# Sampling_Detector.net
KiCad netlist of a schematic drawn in EAGLE
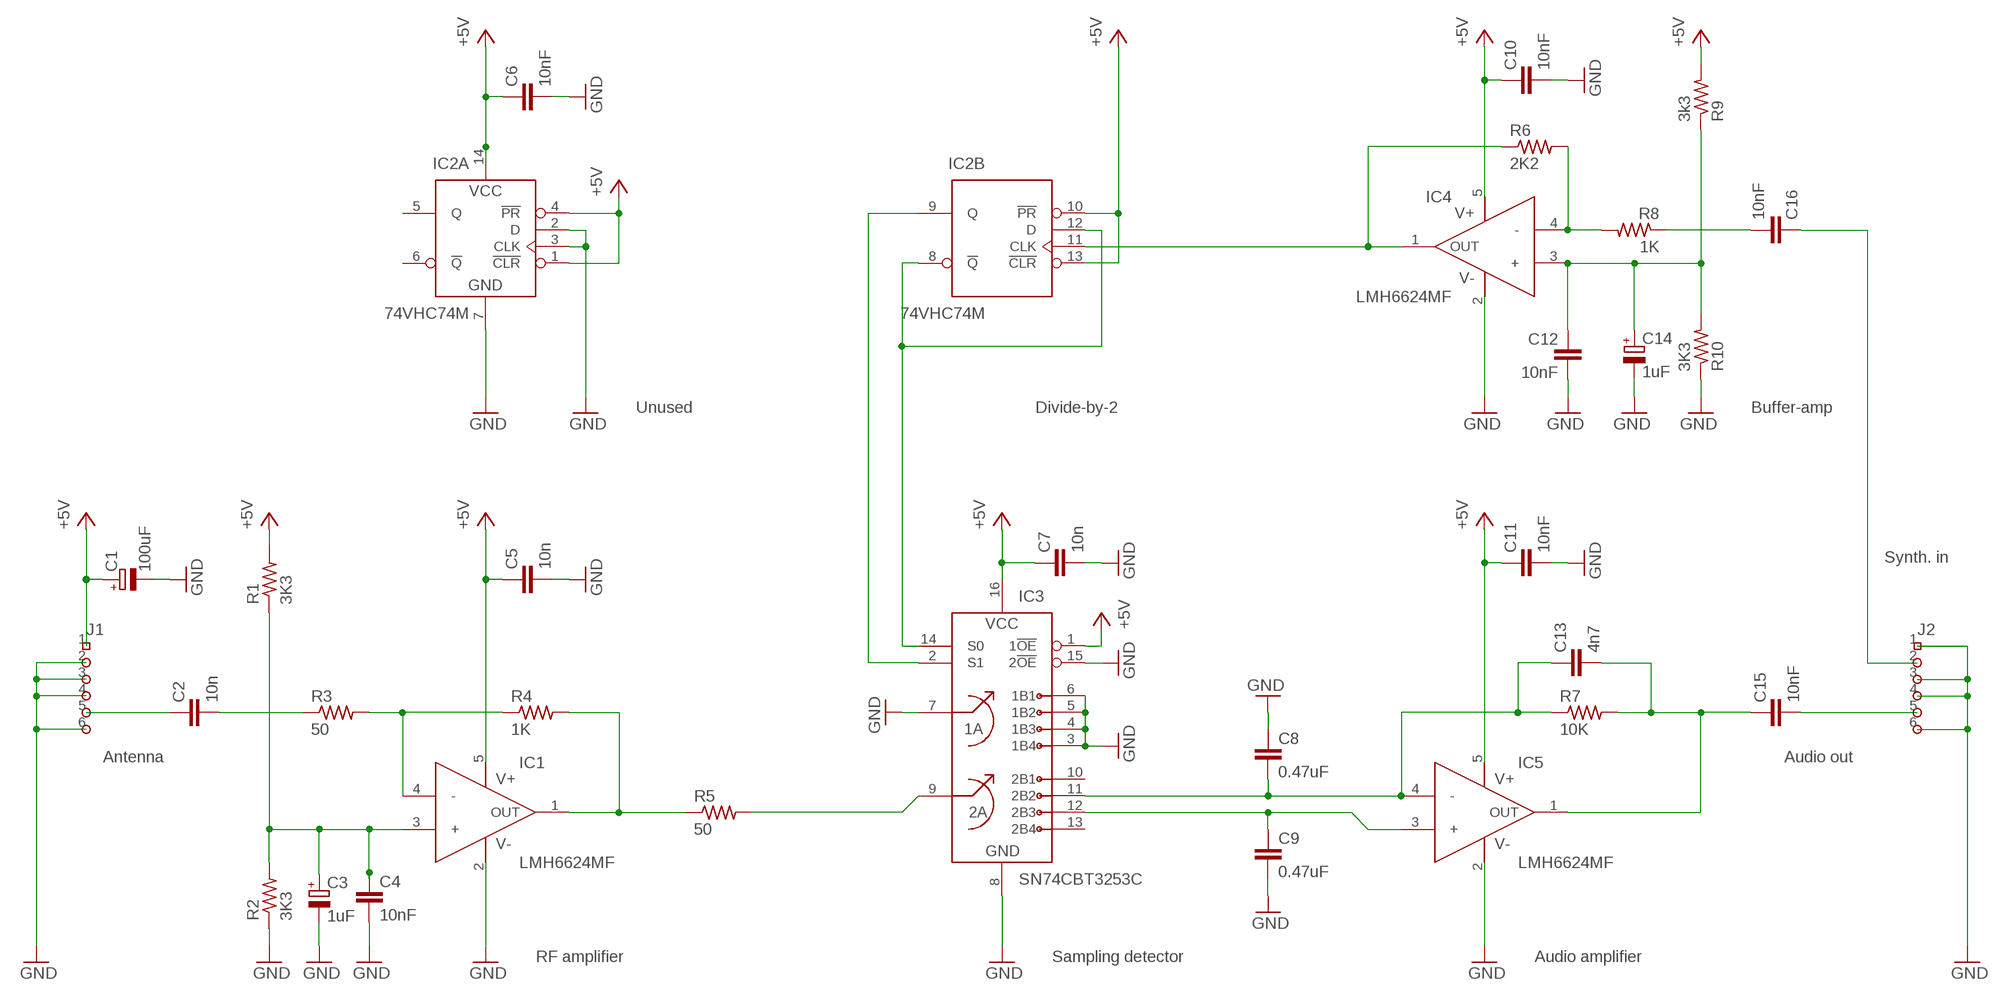
[diagram p0: schematic, sheet 1]

(export (version "E")
  (design (tool "Eeschema 10.0.6"))
  (components
    (comp (ref "C1")
      (value "100uF")
      (footprint "eagle-import:E5.8-8")
      (libsource (lib "eagle-import") (part "ELECTROLYTIC-PIGTAIL"))
    )
    (comp (ref "C2")
      (value "10n")
      (footprint "eagle-import:SMD-0805")
      (libsource (lib "eagle-import") (part "CAPACITOR-0805"))
    )
    (comp (ref "C3")
      (value "1uF")
      (footprint "eagle-import:SMD-0805")
      (libsource (lib "eagle-import") (part "ELECTROLYTIC-0805"))
    )
    (comp (ref "C4")
      (value "10nF")
      (footprint "eagle-import:SMD-0805")
      (libsource (lib "eagle-import") (part "CAPACITOR-0805"))
    )
    (comp (ref "C5")
      (value "10n")
      (footprint "eagle-import:SMD-0805")
      (libsource (lib "eagle-import") (part "CAPACITOR-0805"))
    )
    (comp (ref "C6")
      (value "10nF")
      (footprint "eagle-import:SMD-0805")
      (libsource (lib "eagle-import") (part "CAPACITOR-0805"))
    )
    (comp (ref "C7")
      (value "10n")
      (footprint "eagle-import:SMD-0805")
      (libsource (lib "eagle-import") (part "CAPACITOR-0805"))
    )
    (comp (ref "C8")
      (value "0.47uF")
      (footprint "eagle-import:SMD-0805")
      (libsource (lib "eagle-import") (part "CAPACITOR-0805"))
    )
    (comp (ref "C9")
      (value "0.47uF")
      (footprint "eagle-import:SMD-0805")
      (libsource (lib "eagle-import") (part "CAPACITOR-0805"))
    )
    (comp (ref "C10")
      (value "10nF")
      (footprint "eagle-import:SMD-0805")
      (libsource (lib "eagle-import") (part "CAPACITOR-0805"))
    )
    (comp (ref "C11")
      (value "10nF")
      (footprint "eagle-import:SMD-0805")
      (libsource (lib "eagle-import") (part "CAPACITOR-0805"))
    )
    (comp (ref "C12")
      (value "10nF")
      (footprint "eagle-import:SMD-0805")
      (libsource (lib "eagle-import") (part "CAPACITOR-0805"))
    )
    (comp (ref "C13")
      (value "4n7")
      (footprint "eagle-import:SMD-0805")
      (libsource (lib "eagle-import") (part "CAPACITOR-0805"))
    )
    (comp (ref "C14")
      (value "1uF")
      (footprint "eagle-import:SMD-0805")
      (libsource (lib "eagle-import") (part "ELECTROLYTIC-0805"))
    )
    (comp (ref "C15")
      (value "10nF")
      (footprint "eagle-import:SMD-0805")
      (libsource (lib "eagle-import") (part "CAPACITOR-0805"))
    )
    (comp (ref "C16")
      (value "10nF")
      (footprint "eagle-import:SMD-0805")
      (libsource (lib "eagle-import") (part "CAPACITOR-0805"))
    )
    (comp (ref "IC1")
      (value "LMH6624MF")
      (footprint "eagle-import:SOT-23-DBV")
      (libsource (lib "eagle-import") (part "LMH6624MF"))
    )
    (comp (ref "IC2")
      (value "74VHC74M")
      (footprint "eagle-import:SOIC-14PIN")
      (libsource (lib "eagle-import") (part "74VHC74M"))
    )
    (comp (ref "IC3")
      (value "SN74CBT3253C")
      (footprint "eagle-import:SOIC-16PIN")
      (libsource (lib "eagle-import") (part "SN74CBT3253C"))
    )
    (comp (ref "IC4")
      (value "LMH6624MF")
      (footprint "eagle-import:SOT-23-DBV")
      (libsource (lib "eagle-import") (part "LMH6624MF"))
    )
    (comp (ref "IC5")
      (value "LMH6624MF")
      (footprint "eagle-import:SOT-23-DBV")
      (libsource (lib "eagle-import") (part "LMH6624MF"))
    )
    (comp (ref "J1")
      (value "TERM-STRIP-6PIN")
      (footprint "eagle-import:TERM-STRIP-6PIN")
      (libsource (lib "eagle-import") (part "TERM-STRIP-6PIN"))
    )
    (comp (ref "J2")
      (value "TERM-STRIP-6PIN")
      (footprint "eagle-import:TERM-STRIP-6PIN")
      (libsource (lib "eagle-import") (part "TERM-STRIP-6PIN"))
    )
    (comp (ref "R1")
      (value "3K3")
      (footprint "eagle-import:SMD-0805")
      (libsource (lib "eagle-import") (part "RESISTOR-0805"))
    )
    (comp (ref "R2")
      (value "3K3")
      (footprint "eagle-import:SMD-0805")
      (libsource (lib "eagle-import") (part "RESISTOR-0805"))
    )
    (comp (ref "R3")
      (value "50")
      (footprint "eagle-import:SMD-0805")
      (libsource (lib "eagle-import") (part "RESISTOR-0805"))
    )
    (comp (ref "R4")
      (value "1K")
      (footprint "eagle-import:SMD-0805")
      (libsource (lib "eagle-import") (part "RESISTOR-0805"))
    )
    (comp (ref "R5")
      (value "50")
      (footprint "eagle-import:SMD-0805")
      (libsource (lib "eagle-import") (part "RESISTOR-0805"))
    )
    (comp (ref "R6")
      (value "2K2")
      (footprint "eagle-import:SMD-0805")
      (libsource (lib "eagle-import") (part "RESISTOR-0805"))
    )
    (comp (ref "R7")
      (value "10K")
      (footprint "eagle-import:SMD-0805")
      (libsource (lib "eagle-import") (part "RESISTOR-0805"))
    )
    (comp (ref "R8")
      (value "1K")
      (footprint "eagle-import:SMD-0805")
      (libsource (lib "eagle-import") (part "RESISTOR-0805"))
    )
    (comp (ref "R9")
      (value "3k3")
      (footprint "eagle-import:SMD-0805")
      (libsource (lib "eagle-import") (part "RESISTOR-0805"))
    )
    (comp (ref "R10")
      (value "3K3")
      (footprint "eagle-import:SMD-0805")
      (libsource (lib "eagle-import") (part "RESISTOR-0805"))
    )
  )
  (nets
    (net (code "1") (name "+5V") (class "Default")
      (node (ref "C1") (pin "1") (pinfunction "+_1") (pintype "passive"))
      (node (ref "C10") (pin "1") (pinfunction "1_1") (pintype "passive"))
      (node (ref "C11") (pin "1") (pinfunction "1_1") (pintype "passive"))
      (node (ref "C5") (pin "1") (pinfunction "1_1") (pintype "passive"))
      (node (ref "C6") (pin "1") (pinfunction "1_1") (pintype "passive"))
      (node (ref "C7") (pin "1") (pinfunction "1_1") (pintype "passive"))
      (node (ref "IC1") (pin "5") (pinfunction "V+_5") (pintype "power_in"))
      (node (ref "IC2") (pin "1") (pinfunction "~{CLR}_1") (pintype "input"))
      (node (ref "IC2") (pin "10") (pinfunction "~{PR}_10") (pintype "input"))
      (node (ref "IC2") (pin "13") (pinfunction "~{CLR}_13") (pintype "input"))
      (node (ref "IC2") (pin "14") (pinfunction "VCC_14") (pintype "power_in"))
      (node (ref "IC2") (pin "4") (pinfunction "~{PR}_4") (pintype "input"))
      (node (ref "IC3") (pin "1") (pinfunction "1~{OE}_1") (pintype "input"))
      (node (ref "IC3") (pin "16") (pinfunction "VCC_16") (pintype "power_in"))
      (node (ref "IC4") (pin "5") (pinfunction "V+_5") (pintype "power_in"))
      (node (ref "IC5") (pin "5") (pinfunction "V+_5") (pintype "power_in"))
      (node (ref "J1") (pin "1") (pinfunction "1_1") (pintype "bidirectional"))
      (node (ref "R1") (pin "2") (pinfunction "2_2") (pintype "passive"))
      (node (ref "R9") (pin "2") (pinfunction "2_2") (pintype "passive"))
    )
    (net (code "2") (name "GND") (class "Default")
      (node (ref "C1") (pin "2") (pinfunction "-_2") (pintype "passive"))
      (node (ref "C10") (pin "2") (pinfunction "2_2") (pintype "passive"))
      (node (ref "C11") (pin "2") (pinfunction "2_2") (pintype "passive"))
      (node (ref "C12") (pin "2") (pinfunction "2_2") (pintype "passive"))
      (node (ref "C14") (pin "2") (pinfunction "-_2") (pintype "passive"))
      (node (ref "C3") (pin "2") (pinfunction "-_2") (pintype "passive"))
      (node (ref "C4") (pin "2") (pinfunction "2_2") (pintype "passive"))
      (node (ref "C5") (pin "2") (pinfunction "2_2") (pintype "passive"))
      (node (ref "C6") (pin "2") (pinfunction "2_2") (pintype "passive"))
      (node (ref "C7") (pin "2") (pinfunction "2_2") (pintype "passive"))
      (node (ref "C8") (pin "1") (pinfunction "1_1") (pintype "passive"))
      (node (ref "C9") (pin "2") (pinfunction "2_2") (pintype "passive"))
      (node (ref "IC1") (pin "2") (pinfunction "V-_2") (pintype "power_in"))
      (node (ref "IC2") (pin "2") (pinfunction "D_2") (pintype "input"))
      (node (ref "IC2") (pin "3") (pinfunction "CLK_3") (pintype "input"))
      (node (ref "IC2") (pin "7") (pinfunction "GND_7") (pintype "power_in"))
      (node (ref "IC3") (pin "15") (pinfunction "2~{OE}_15") (pintype "input"))
      (node (ref "IC3") (pin "3") (pinfunction "1B4_3") (pintype "output"))
      (node (ref "IC3") (pin "4") (pinfunction "1B3_4") (pintype "output"))
      (node (ref "IC3") (pin "5") (pinfunction "1B2_5") (pintype "output"))
      (node (ref "IC3") (pin "6") (pinfunction "1B1_6") (pintype "output"))
      (node (ref "IC3") (pin "7") (pinfunction "1A_7") (pintype "input"))
      (node (ref "IC3") (pin "8") (pinfunction "GND_8") (pintype "power_in"))
      (node (ref "IC4") (pin "2") (pinfunction "V-_2") (pintype "power_in"))
      (node (ref "IC5") (pin "2") (pinfunction "V-_2") (pintype "power_in"))
      (node (ref "J1") (pin "2") (pinfunction "2_2") (pintype "bidirectional"))
      (node (ref "J1") (pin "3") (pinfunction "3_3") (pintype "bidirectional"))
      (node (ref "J1") (pin "4") (pinfunction "4_4") (pintype "bidirectional"))
      (node (ref "J1") (pin "6") (pinfunction "6_6") (pintype "bidirectional"))
      (node (ref "J2") (pin "1") (pinfunction "1_1") (pintype "bidirectional"))
      (node (ref "J2") (pin "3") (pinfunction "3_3") (pintype "bidirectional"))
      (node (ref "J2") (pin "4") (pinfunction "4_4") (pintype "bidirectional"))
      (node (ref "J2") (pin "6") (pinfunction "6_6") (pintype "bidirectional"))
      (node (ref "R10") (pin "1") (pinfunction "1_1") (pintype "passive"))
      (node (ref "R2") (pin "1") (pinfunction "1_1") (pintype "passive"))
    )
    (net (code "3") (name "Net-(C2-Pad1)") (class "Default")
      (node (ref "C2") (pin "1") (pinfunction "1_1") (pintype "passive"))
      (node (ref "J1") (pin "5") (pinfunction "5_5") (pintype "bidirectional"))
    )
    (net (code "4") (name "Net-(C2-Pad2)") (class "Default")
      (node (ref "C2") (pin "2") (pinfunction "2_2") (pintype "passive"))
      (node (ref "R3") (pin "1") (pinfunction "1_1") (pintype "passive"))
    )
    (net (code "5") (name "Net-(C3-+)") (class "Default")
      (node (ref "C3") (pin "1") (pinfunction "+_1") (pintype "passive"))
      (node (ref "C4") (pin "1") (pinfunction "1_1") (pintype "passive"))
      (node (ref "IC1") (pin "3") (pinfunction "+_3") (pintype "input"))
      (node (ref "R1") (pin "1") (pinfunction "1_1") (pintype "passive"))
      (node (ref "R2") (pin "2") (pinfunction "2_2") (pintype "passive"))
    )
    (net (code "6") (name "Net-(C14-+)") (class "Default")
      (node (ref "C12") (pin "1") (pinfunction "1_1") (pintype "passive"))
      (node (ref "C14") (pin "1") (pinfunction "+_1") (pintype "passive"))
      (node (ref "IC4") (pin "3") (pinfunction "+_3") (pintype "input"))
      (node (ref "R10") (pin "2") (pinfunction "2_2") (pintype "passive"))
      (node (ref "R9") (pin "1") (pinfunction "1_1") (pintype "passive"))
    )
    (net (code "7") (name "Net-(C15-Pad2)") (class "Default")
      (node (ref "C15") (pin "2") (pinfunction "2_2") (pintype "passive"))
      (node (ref "J2") (pin "5") (pinfunction "5_5") (pintype "bidirectional"))
    )
    (net (code "8") (name "Net-(C16-Pad1)") (class "Default")
      (node (ref "C16") (pin "1") (pinfunction "1_1") (pintype "passive"))
      (node (ref "J2") (pin "2") (pinfunction "2_2") (pintype "bidirectional"))
    )
    (net (code "9") (name "Net-(C16-Pad2)") (class "Default")
      (node (ref "C16") (pin "2") (pinfunction "2_2") (pintype "passive"))
      (node (ref "R8") (pin "1") (pinfunction "1_1") (pintype "passive"))
    )
    (net (code "10") (name "Net-(IC1--)") (class "Default")
      (node (ref "IC1") (pin "4") (pinfunction "-_4") (pintype "input"))
      (node (ref "R3") (pin "2") (pinfunction "2_2") (pintype "passive"))
      (node (ref "R4") (pin "1") (pinfunction "1_1") (pintype "passive"))
    )
    (net (code "11") (name "Net-(IC1-OUT)") (class "Default")
      (node (ref "IC1") (pin "1") (pinfunction "OUT_1") (pintype "output"))
      (node (ref "R4") (pin "2") (pinfunction "2_2") (pintype "passive"))
      (node (ref "R5") (pin "1") (pinfunction "1_1") (pintype "passive"))
    )
    (net (code "12") (name "Net-(IC2B-CLK)") (class "Default")
      (node (ref "IC2") (pin "11") (pinfunction "CLK_11") (pintype "input"))
      (node (ref "IC4") (pin "1") (pinfunction "OUT_1") (pintype "output"))
      (node (ref "R6") (pin "1") (pinfunction "1_1") (pintype "passive"))
    )
    (net (code "13") (name "Net-(IC2B-D)") (class "Default")
      (node (ref "IC2") (pin "12") (pinfunction "D_12") (pintype "input"))
      (node (ref "IC2") (pin "8") (pinfunction "~{Q}_8") (pintype "output"))
      (node (ref "IC3") (pin "14") (pinfunction "S0_14") (pintype "input"))
    )
    (net (code "14") (name "Net-(IC2B-Q)") (class "Default")
      (node (ref "IC2") (pin "9") (pinfunction "Q_9") (pintype "output"))
      (node (ref "IC3") (pin "2") (pinfunction "S1_2") (pintype "input"))
    )
    (net (code "15") (name "Net-(IC3-2A)") (class "Default")
      (node (ref "IC3") (pin "9") (pinfunction "2A_9") (pintype "input"))
      (node (ref "R5") (pin "2") (pinfunction "2_2") (pintype "passive"))
    )
    (net (code "16") (name "Net-(IC3-2B2)") (class "Default")
      (node (ref "C13") (pin "1") (pinfunction "1_1") (pintype "passive"))
      (node (ref "C8") (pin "2") (pinfunction "2_2") (pintype "passive"))
      (node (ref "IC3") (pin "11") (pinfunction "2B2_11") (pintype "output"))
      (node (ref "IC5") (pin "4") (pinfunction "-_4") (pintype "input"))
      (node (ref "R7") (pin "1") (pinfunction "1_1") (pintype "passive"))
    )
    (net (code "17") (name "Net-(IC3-2B3)") (class "Default")
      (node (ref "C9") (pin "1") (pinfunction "1_1") (pintype "passive"))
      (node (ref "IC3") (pin "12") (pinfunction "2B3_12") (pintype "output"))
      (node (ref "IC5") (pin "3") (pinfunction "+_3") (pintype "input"))
    )
    (net (code "18") (name "Net-(IC4--)") (class "Default")
      (node (ref "IC4") (pin "4") (pinfunction "-_4") (pintype "input"))
      (node (ref "R6") (pin "2") (pinfunction "2_2") (pintype "passive"))
      (node (ref "R8") (pin "2") (pinfunction "2_2") (pintype "passive"))
    )
    (net (code "19") (name "Net-(IC5-OUT)") (class "Default")
      (node (ref "C13") (pin "2") (pinfunction "2_2") (pintype "passive"))
      (node (ref "C15") (pin "1") (pinfunction "1_1") (pintype "passive"))
      (node (ref "IC5") (pin "1") (pinfunction "OUT_1") (pintype "output"))
      (node (ref "R7") (pin "2") (pinfunction "2_2") (pintype "passive"))
    )
    (net (code "20") (name "unconnected-(IC2A-Q-Pad5)") (class "Default")
      (node (ref "IC2") (pin "5") (pinfunction "Q_5") (pintype "output"))
    )
    (net (code "21") (name "unconnected-(IC2A-~{Q}-Pad6)") (class "Default")
      (node (ref "IC2") (pin "6") (pinfunction "~{Q}_6") (pintype "output"))
    )
    (net (code "22") (name "unconnected-(IC3-2B1-Pad10)") (class "Default")
      (node (ref "IC3") (pin "10") (pinfunction "2B1_10") (pintype "output"))
    )
    (net (code "23") (name "unconnected-(IC3-2B4-Pad13)") (class "Default")
      (node (ref "IC3") (pin "13") (pinfunction "2B4_13") (pintype "output"))
    )
  )
)
